# schematic.net
KiCad netlist of a schematic drawn in EAGLE
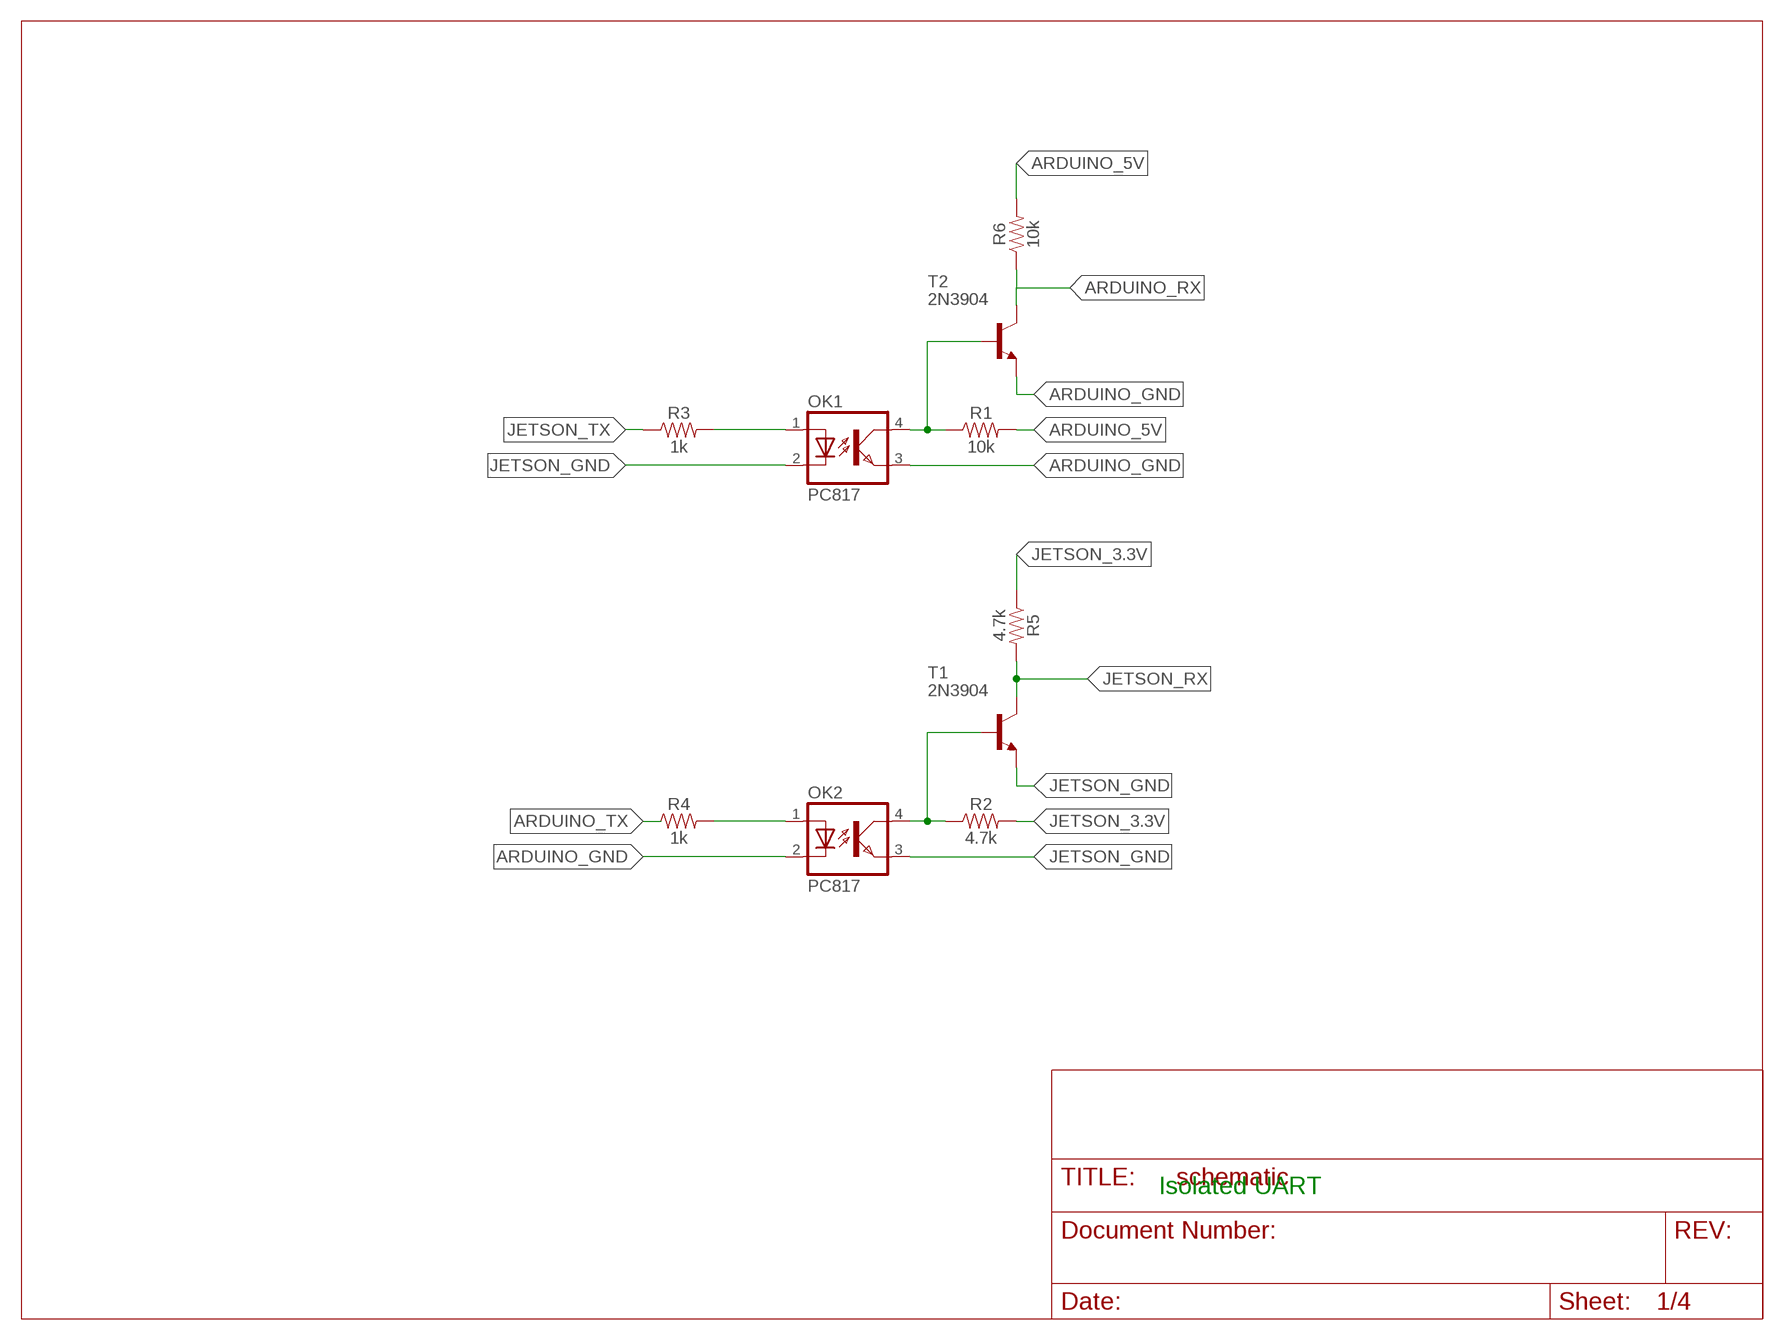
[diagram p0: schematic, sheet 1]
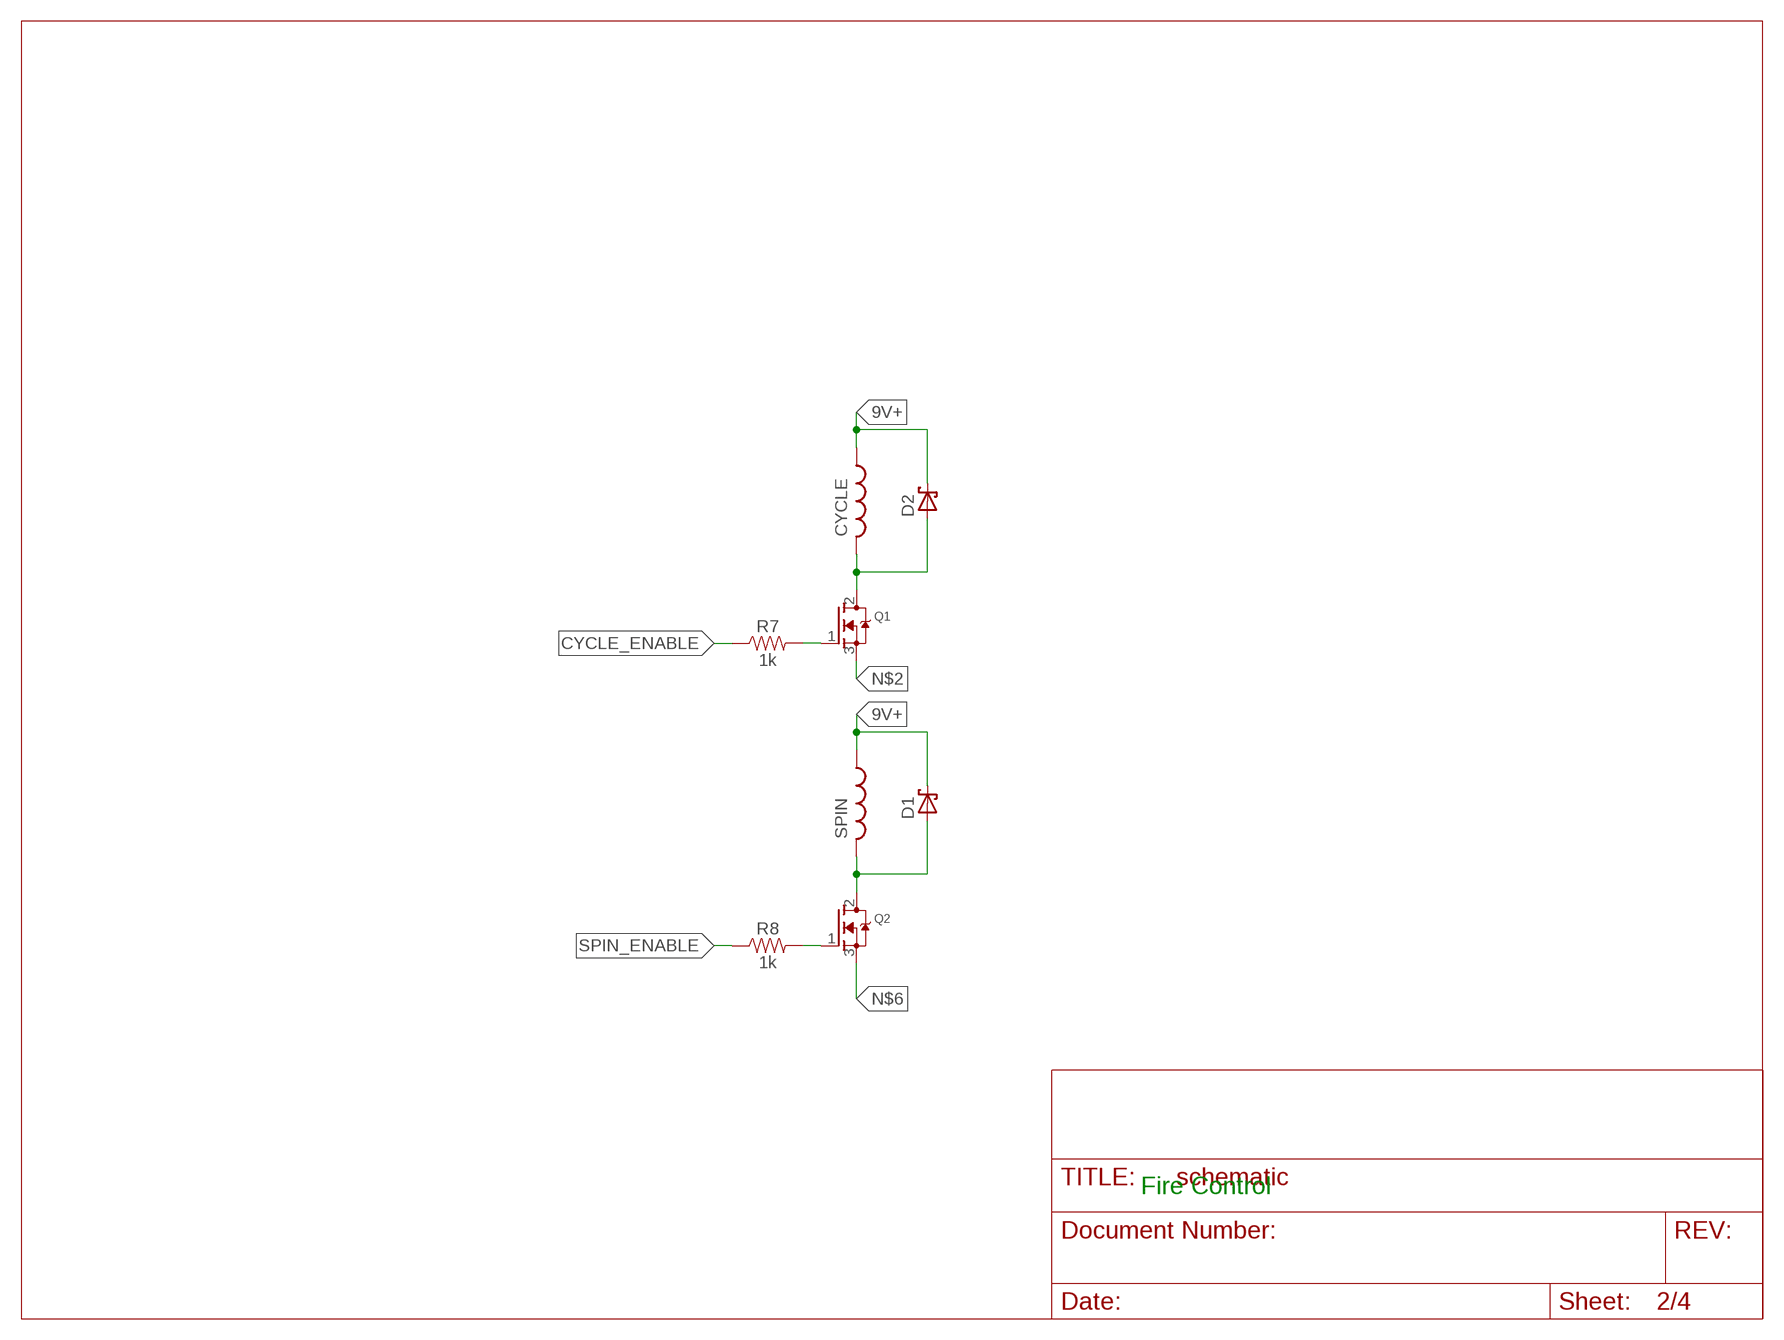
[diagram p1: schematic, sheet 2]
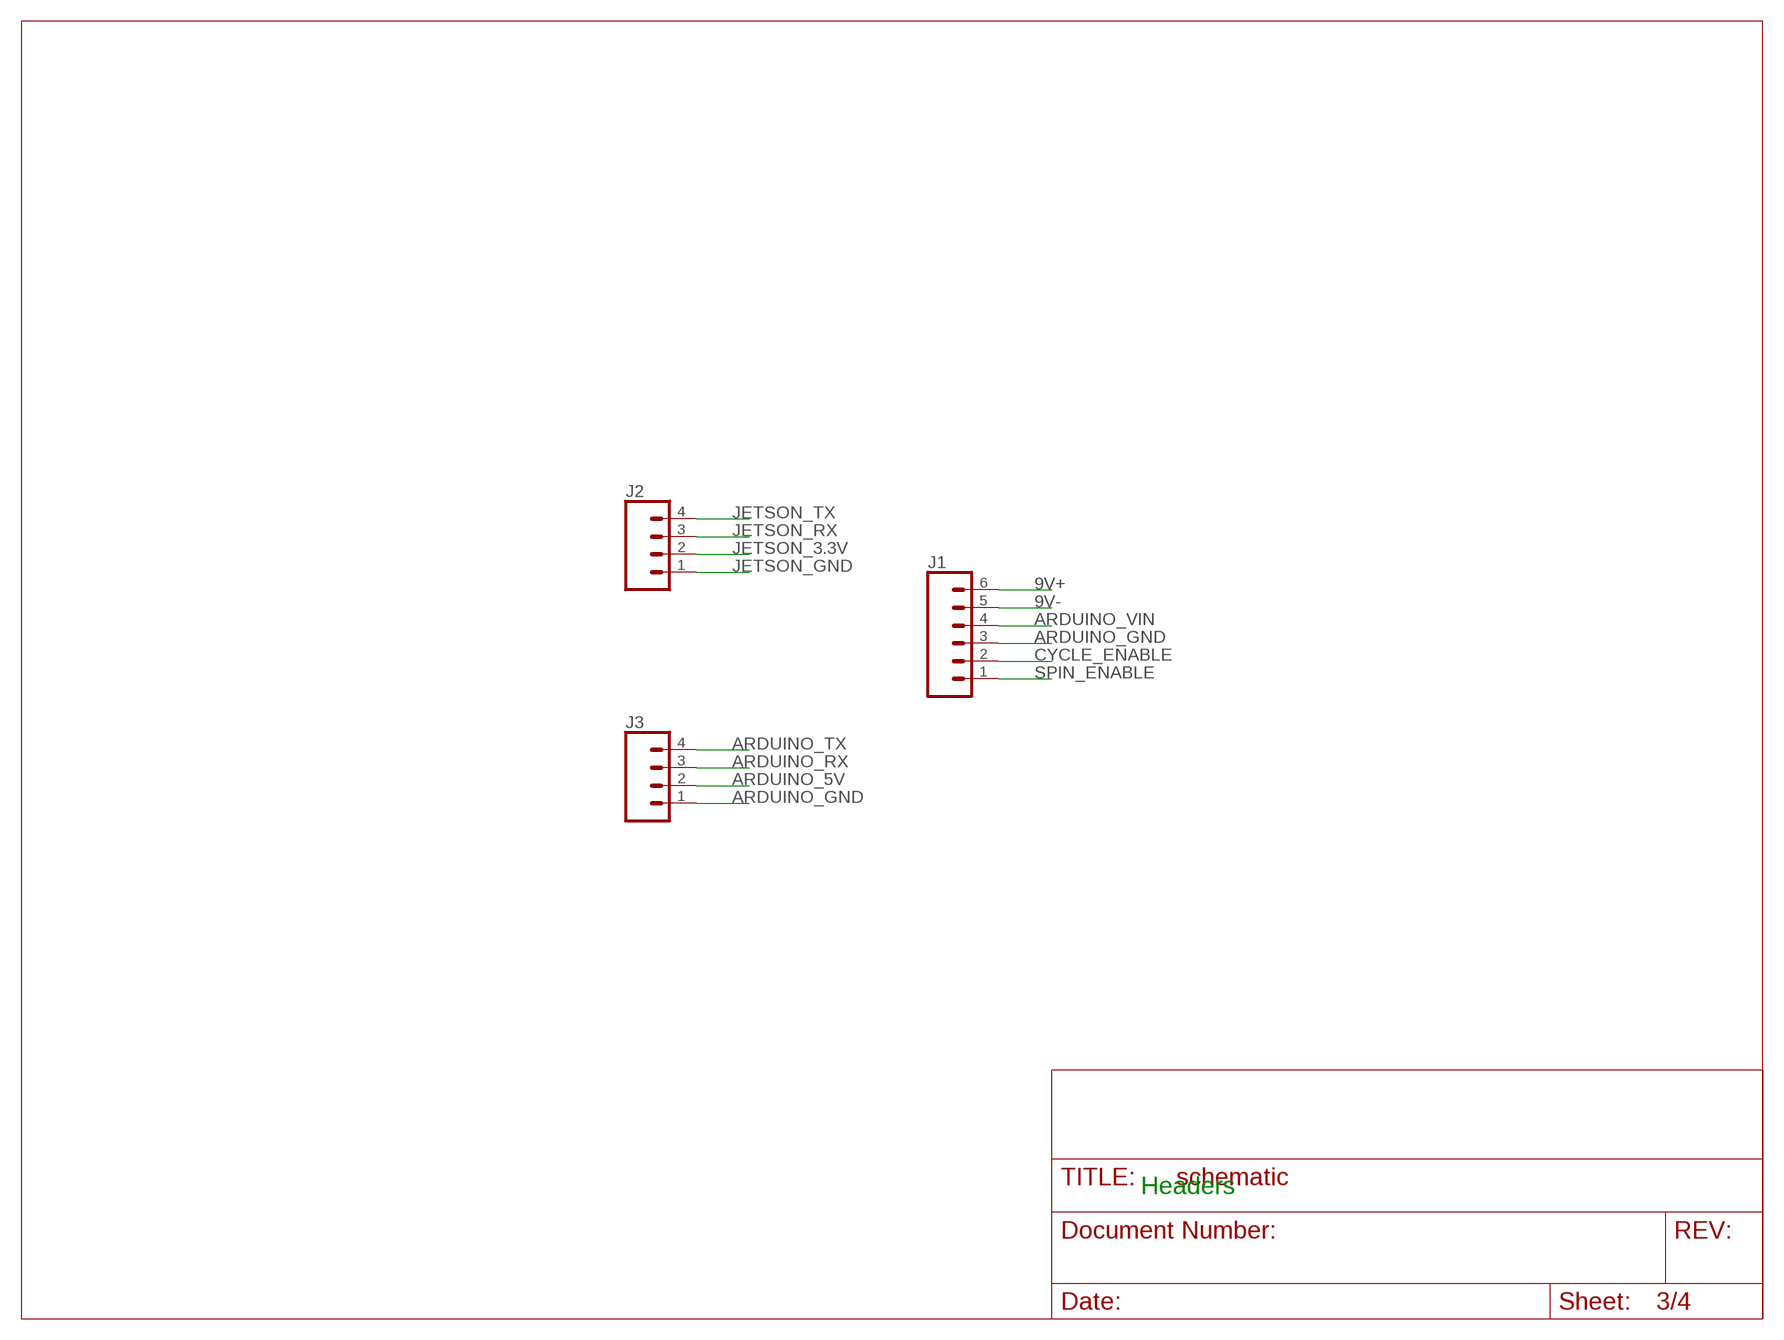
[diagram p2: schematic, sheet 3]
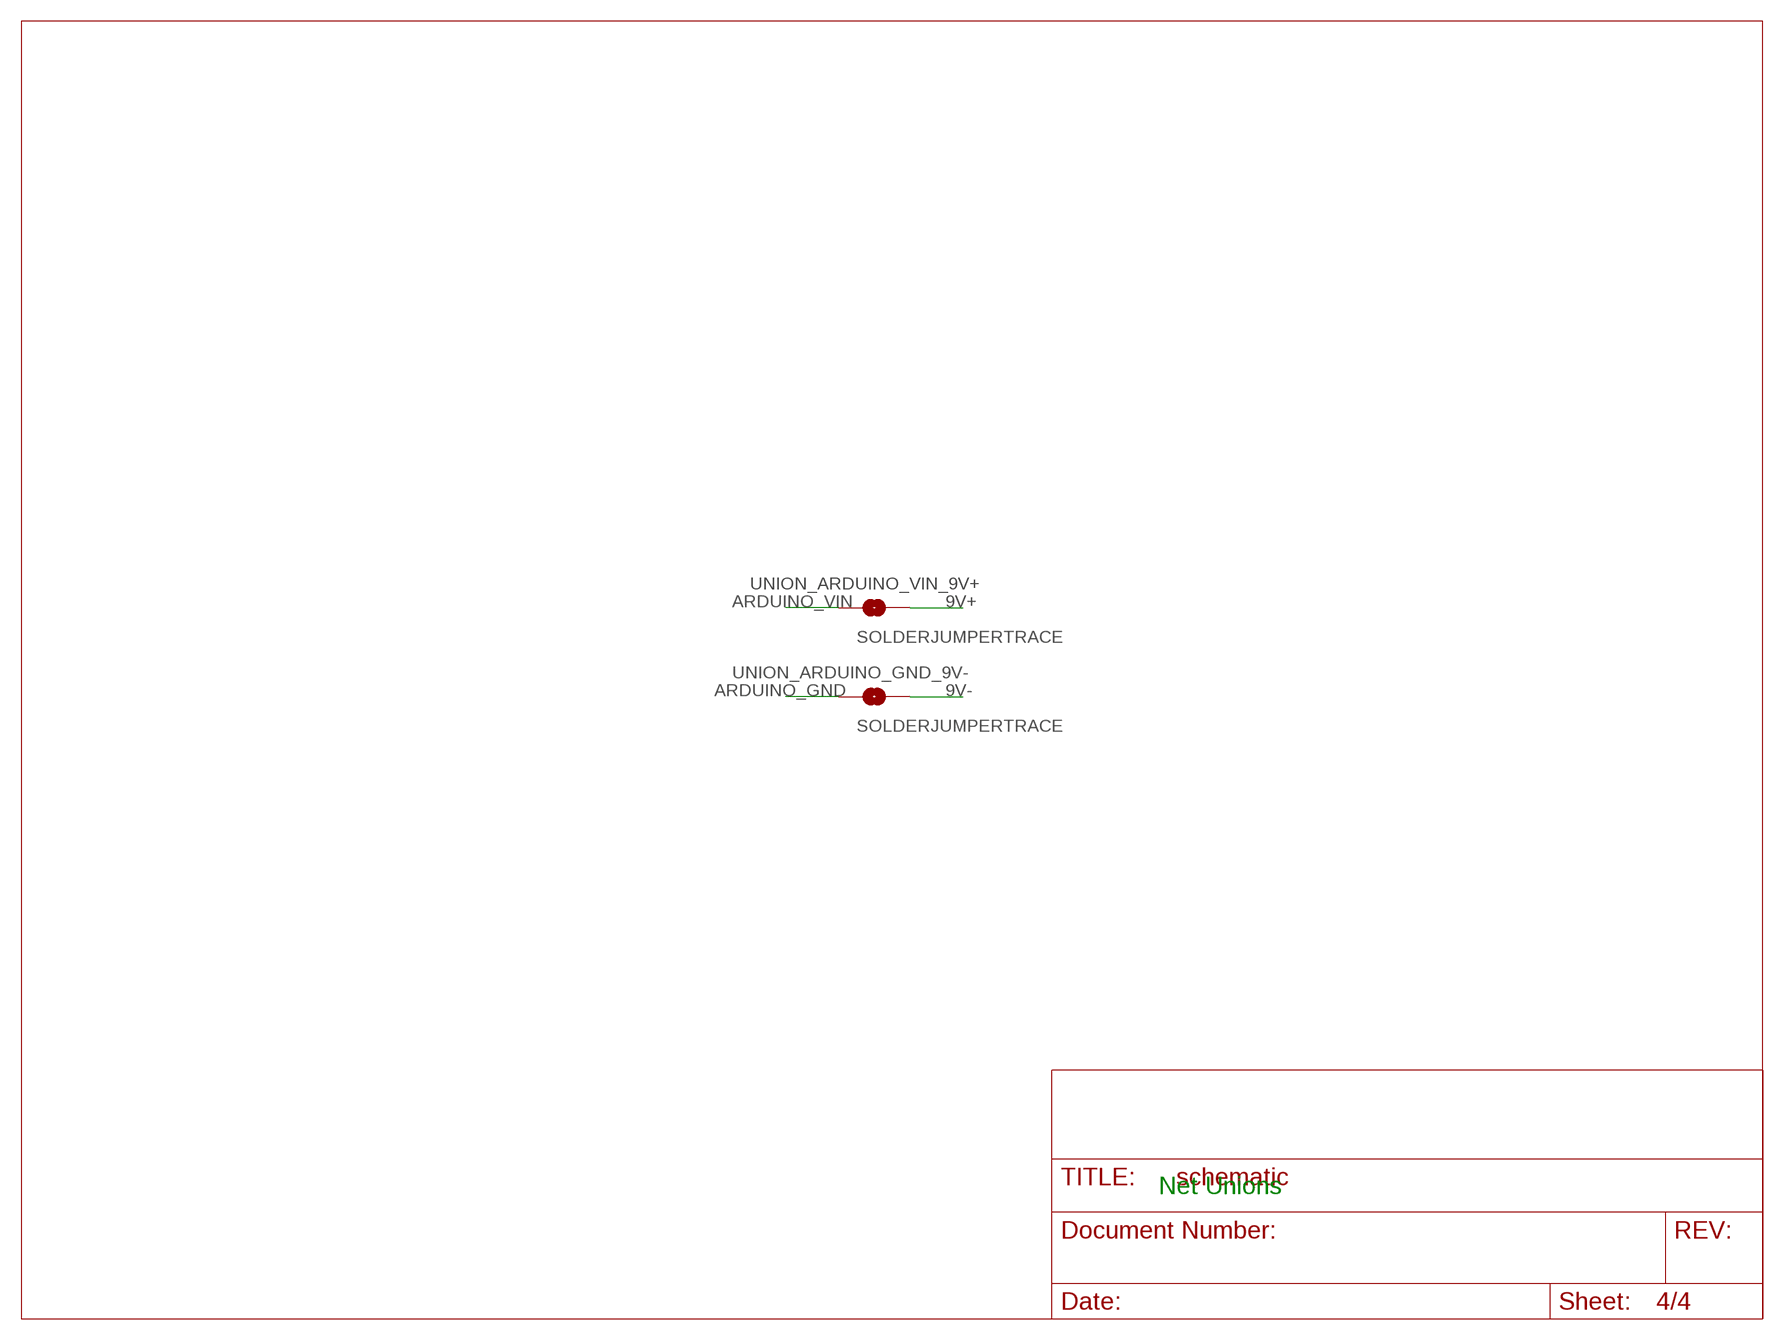
[diagram p3: schematic, sheet 4]

(export (version "E")
  (design (tool "Eeschema 10.0.6"))
  (components
    (comp (ref "OK1")
      (value "PC817")
      (footprint "eagle-import:DIL04")
      (fields (field (name "MPN") "PC817X4J000F"))
      (libsource (lib "eagle-import") (part "PC817"))
    )
    (comp (ref "OK2")
      (value "PC817")
      (footprint "eagle-import:DIL04")
      (fields (field (name "MPN") "PC817X4J000F"))
      (libsource (lib "eagle-import") (part "PC817"))
    )
    (comp (ref "R1")
      (value "10k")
      (footprint "eagle-import:AXIAL-0.3")
      (libsource (lib "eagle-import") (part "1KOHM-HORIZ-1/4W-1%"))
    )
    (comp (ref "R2")
      (value "4.7k")
      (footprint "eagle-import:AXIAL-0.3")
      (libsource (lib "eagle-import") (part "1KOHM-HORIZ-1/4W-1%"))
    )
    (comp (ref "R3")
      (value "1k")
      (footprint "eagle-import:AXIAL-0.3")
      (libsource (lib "eagle-import") (part "1KOHM-HORIZ-1/4W-1%"))
    )
    (comp (ref "R4")
      (value "1k")
      (footprint "eagle-import:AXIAL-0.3")
      (libsource (lib "eagle-import") (part "1KOHM-HORIZ-1/4W-1%"))
    )
    (comp (ref "R5")
      (value "4.7k")
      (footprint "eagle-import:AXIAL-0.3")
      (libsource (lib "eagle-import") (part "1KOHM-HORIZ-1/4W-1%"))
    )
    (comp (ref "R6")
      (value "10k")
      (footprint "eagle-import:AXIAL-0.3")
      (libsource (lib "eagle-import") (part "1KOHM-HORIZ-1/4W-1%"))
    )
    (comp (ref "T1")
      (value "2N3904")
      (footprint "eagle-import:TO92")
      (libsource (lib "eagle-import") (part "2N3904"))
    )
    (comp (ref "T2")
      (value "2N3904")
      (footprint "eagle-import:TO92")
      (libsource (lib "eagle-import") (part "2N3904"))
    )
    (comp (ref "J1")
      (value "CONN_06SILK_FEMALE_PTH")
      (footprint "eagle-import:1X06")
      (libsource (lib "eagle-import") (part "CONN_06SILK_FEMALE_PTH"))
    )
    (comp (ref "J2")
      (value "CONN_04")
      (footprint "eagle-import:1X04")
      (libsource (lib "eagle-import") (part "CONN_04"))
    )
    (comp (ref "J3")
      (value "CONN_04")
      (footprint "eagle-import:1X04")
      (libsource (lib "eagle-import") (part "CONN_04"))
    )
    (comp (ref "CYCLE")
      (value "L-US0204/5")
      (footprint "eagle-import:0204_5")
      (libsource (lib "eagle-import") (part "L-US0204/5"))
    )
    (comp (ref "D1")
      (value "SCHOTTKY-DIODECB417-15")
      (footprint "eagle-import:CB417-15")
      (libsource (lib "eagle-import") (part "SCHOTTKY-DIODECB417-15"))
    )
    (comp (ref "D2")
      (value "SCHOTTKY-DIODECB417-15")
      (footprint "eagle-import:CB417-15")
      (libsource (lib "eagle-import") (part "SCHOTTKY-DIODECB417-15"))
    )
    (comp (ref "Q1")
      (value "MOSFET-NGDS_TO220V")
      (footprint "eagle-import:TO220V")
      (libsource (lib "eagle-import") (part "MOSFET-NGDS_TO220V"))
    )
    (comp (ref "Q2")
      (value "MOSFET-NGDS_TO220V")
      (footprint "eagle-import:TO220V")
      (libsource (lib "eagle-import") (part "MOSFET-NGDS_TO220V"))
    )
    (comp (ref "R7")
      (value "1k")
      (footprint "eagle-import:AXIAL-0.3")
      (libsource (lib "eagle-import") (part "SparkFun-Resistors_532_1KOHM-HORIZ-1/4W-5%"))
    )
    (comp (ref "R8")
      (value "1k")
      (footprint "eagle-import:AXIAL-0.3")
      (libsource (lib "eagle-import") (part "SparkFun-Resistors_532_1KOHM-HORIZ-1/4W-5%"))
    )
    (comp (ref "SPIN")
      (value "L-US0204/5")
      (footprint "eagle-import:0204_5")
      (libsource (lib "eagle-import") (part "L-US0204/5"))
    )
    (comp (ref "UNION_ARDUINO_GND_9V-")
      (value "SOLDERJUMPERTRACE")
      (footprint "eagle-import:SJ_2S-TRACE")
      (libsource (lib "eagle-import") (part "SOLDERJUMPERTRACE"))
    )
    (comp (ref "UNION_ARDUINO_VIN_9V+")
      (value "SOLDERJUMPERTRACE")
      (footprint "eagle-import:SJ_2S-TRACE")
      (libsource (lib "eagle-import") (part "SOLDERJUMPERTRACE"))
    )
  )
  (nets
    (net (code "1") (name "9V+") (class "Default")
      (node (ref "CYCLE") (pin "1") (pinfunction "1_1") (pintype "passive"))
      (node (ref "D1") (pin "C") (pinfunction "C_C") (pintype "passive"))
      (node (ref "D2") (pin "C") (pinfunction "C_C") (pintype "passive"))
      (node (ref "J1") (pin "6") (pinfunction "6_6") (pintype "passive"))
      (node (ref "SPIN") (pin "1") (pinfunction "1_1") (pintype "passive"))
      (node (ref "UNION_ARDUINO_VIN_9V+") (pin "2") (pinfunction "2_2") (pintype "passive"))
    )
    (net (code "2") (name "9V-") (class "Default")
      (node (ref "CYCLE") (pin "2") (pinfunction "2_2") (pintype "passive"))
      (node (ref "D1") (pin "A") (pinfunction "A_A") (pintype "passive"))
      (node (ref "D2") (pin "A") (pinfunction "A_A") (pintype "passive"))
      (node (ref "J1") (pin "5") (pinfunction "5_5") (pintype "passive"))
      (node (ref "Q1") (pin "2") (pinfunction "D_2") (pintype "bidirectional"))
      (node (ref "Q2") (pin "2") (pinfunction "D_2") (pintype "bidirectional"))
      (node (ref "SPIN") (pin "2") (pinfunction "2_2") (pintype "passive"))
      (node (ref "UNION_ARDUINO_GND_9V-") (pin "2") (pinfunction "2_2") (pintype "passive"))
    )
    (net (code "3") (name "ARDUINO_5V") (class "Default")
      (node (ref "J3") (pin "2") (pinfunction "2_2") (pintype "passive"))
      (node (ref "R1") (pin "P$2") (pinfunction "2_P$2") (pintype "passive"))
      (node (ref "R6") (pin "P$2") (pinfunction "2_P$2") (pintype "passive"))
    )
    (net (code "4") (name "ARDUINO_GND") (class "Default")
      (node (ref "J1") (pin "3") (pinfunction "3_3") (pintype "passive"))
      (node (ref "J3") (pin "1") (pinfunction "1_1") (pintype "passive"))
      (node (ref "OK1") (pin "3") (pinfunction "EMIT_3") (pintype "passive"))
      (node (ref "OK2") (pin "2") (pinfunction "C_2") (pintype "passive"))
      (node (ref "T2") (pin "3") (pinfunction "E_3") (pintype "passive"))
      (node (ref "UNION_ARDUINO_GND_9V-") (pin "1") (pinfunction "1_1") (pintype "passive"))
    )
    (net (code "5") (name "ARDUINO_RX") (class "Default")
      (node (ref "J3") (pin "3") (pinfunction "3_3") (pintype "passive"))
      (node (ref "R6") (pin "P$1") (pinfunction "1_P$1") (pintype "passive"))
      (node (ref "T2") (pin "1") (pinfunction "C_1") (pintype "passive"))
    )
    (net (code "6") (name "ARDUINO_TX") (class "Default")
      (node (ref "J3") (pin "4") (pinfunction "4_4") (pintype "passive"))
      (node (ref "R4") (pin "P$1") (pinfunction "1_P$1") (pintype "passive"))
    )
    (net (code "7") (name "ARDUINO_VIN") (class "Default")
      (node (ref "J1") (pin "4") (pinfunction "4_4") (pintype "passive"))
      (node (ref "UNION_ARDUINO_VIN_9V+") (pin "1") (pinfunction "1_1") (pintype "passive"))
    )
    (net (code "8") (name "CYCLE_ENABLE") (class "Default")
      (node (ref "J1") (pin "2") (pinfunction "2_2") (pintype "passive"))
      (node (ref "R7") (pin "P$1") (pinfunction "1_P$1") (pintype "passive"))
    )
    (net (code "9") (name "JETSON_3.3V") (class "Default")
      (node (ref "J2") (pin "2") (pinfunction "2_2") (pintype "passive"))
      (node (ref "R2") (pin "P$2") (pinfunction "2_P$2") (pintype "passive"))
      (node (ref "R5") (pin "P$1") (pinfunction "1_P$1") (pintype "passive"))
    )
    (net (code "10") (name "JETSON_GND") (class "Default")
      (node (ref "J2") (pin "1") (pinfunction "1_1") (pintype "passive"))
      (node (ref "OK1") (pin "2") (pinfunction "C_2") (pintype "passive"))
      (node (ref "OK2") (pin "3") (pinfunction "EMIT_3") (pintype "passive"))
      (node (ref "T1") (pin "3") (pinfunction "E_3") (pintype "passive"))
    )
    (net (code "11") (name "JETSON_RX") (class "Default")
      (node (ref "J2") (pin "3") (pinfunction "3_3") (pintype "passive"))
      (node (ref "R5") (pin "P$2") (pinfunction "2_P$2") (pintype "passive"))
      (node (ref "T1") (pin "1") (pinfunction "C_1") (pintype "passive"))
    )
    (net (code "12") (name "JETSON_TX") (class "Default")
      (node (ref "J2") (pin "4") (pinfunction "4_4") (pintype "passive"))
      (node (ref "R3") (pin "P$1") (pinfunction "1_P$1") (pintype "passive"))
    )
    (net (code "13") (name "N$2") (class "Default")
      (node (ref "Q1") (pin "3") (pinfunction "S_3") (pintype "bidirectional"))
    )
    (net (code "14") (name "N$6") (class "Default")
      (node (ref "Q2") (pin "3") (pinfunction "S_3") (pintype "bidirectional"))
    )
    (net (code "15") (name "Net-(OK1-A)") (class "Default")
      (node (ref "OK1") (pin "1") (pinfunction "A_1") (pintype "passive"))
      (node (ref "R3") (pin "P$2") (pinfunction "2_P$2") (pintype "passive"))
    )
    (net (code "16") (name "Net-(OK1-COL)") (class "Default")
      (node (ref "OK1") (pin "4") (pinfunction "COL_4") (pintype "passive"))
      (node (ref "R1") (pin "P$1") (pinfunction "1_P$1") (pintype "passive"))
      (node (ref "T2") (pin "2") (pinfunction "B_2") (pintype "passive"))
    )
    (net (code "17") (name "Net-(OK2-A)") (class "Default")
      (node (ref "OK2") (pin "1") (pinfunction "A_1") (pintype "passive"))
      (node (ref "R4") (pin "P$2") (pinfunction "2_P$2") (pintype "passive"))
    )
    (net (code "18") (name "Net-(OK2-COL)") (class "Default")
      (node (ref "OK2") (pin "4") (pinfunction "COL_4") (pintype "passive"))
      (node (ref "R2") (pin "P$1") (pinfunction "1_P$1") (pintype "passive"))
      (node (ref "T1") (pin "2") (pinfunction "B_2") (pintype "passive"))
    )
    (net (code "19") (name "Net-(Q1-G)") (class "Default")
      (node (ref "Q1") (pin "1") (pinfunction "G_1") (pintype "bidirectional"))
      (node (ref "R7") (pin "P$2") (pinfunction "2_P$2") (pintype "passive"))
    )
    (net (code "20") (name "SPIN_ENABLE") (class "Default")
      (node (ref "J1") (pin "1") (pinfunction "1_1") (pintype "passive"))
      (node (ref "Q2") (pin "1") (pinfunction "G_1") (pintype "bidirectional"))
      (node (ref "R8") (pin "P$1") (pinfunction "1_P$1") (pintype "passive"))
      (node (ref "R8") (pin "P$2") (pinfunction "2_P$2") (pintype "passive"))
    )
  )
)
